# Power_Supply_And_Regulator.net
KiCad netlist of a schematic drawn in Altium Designer
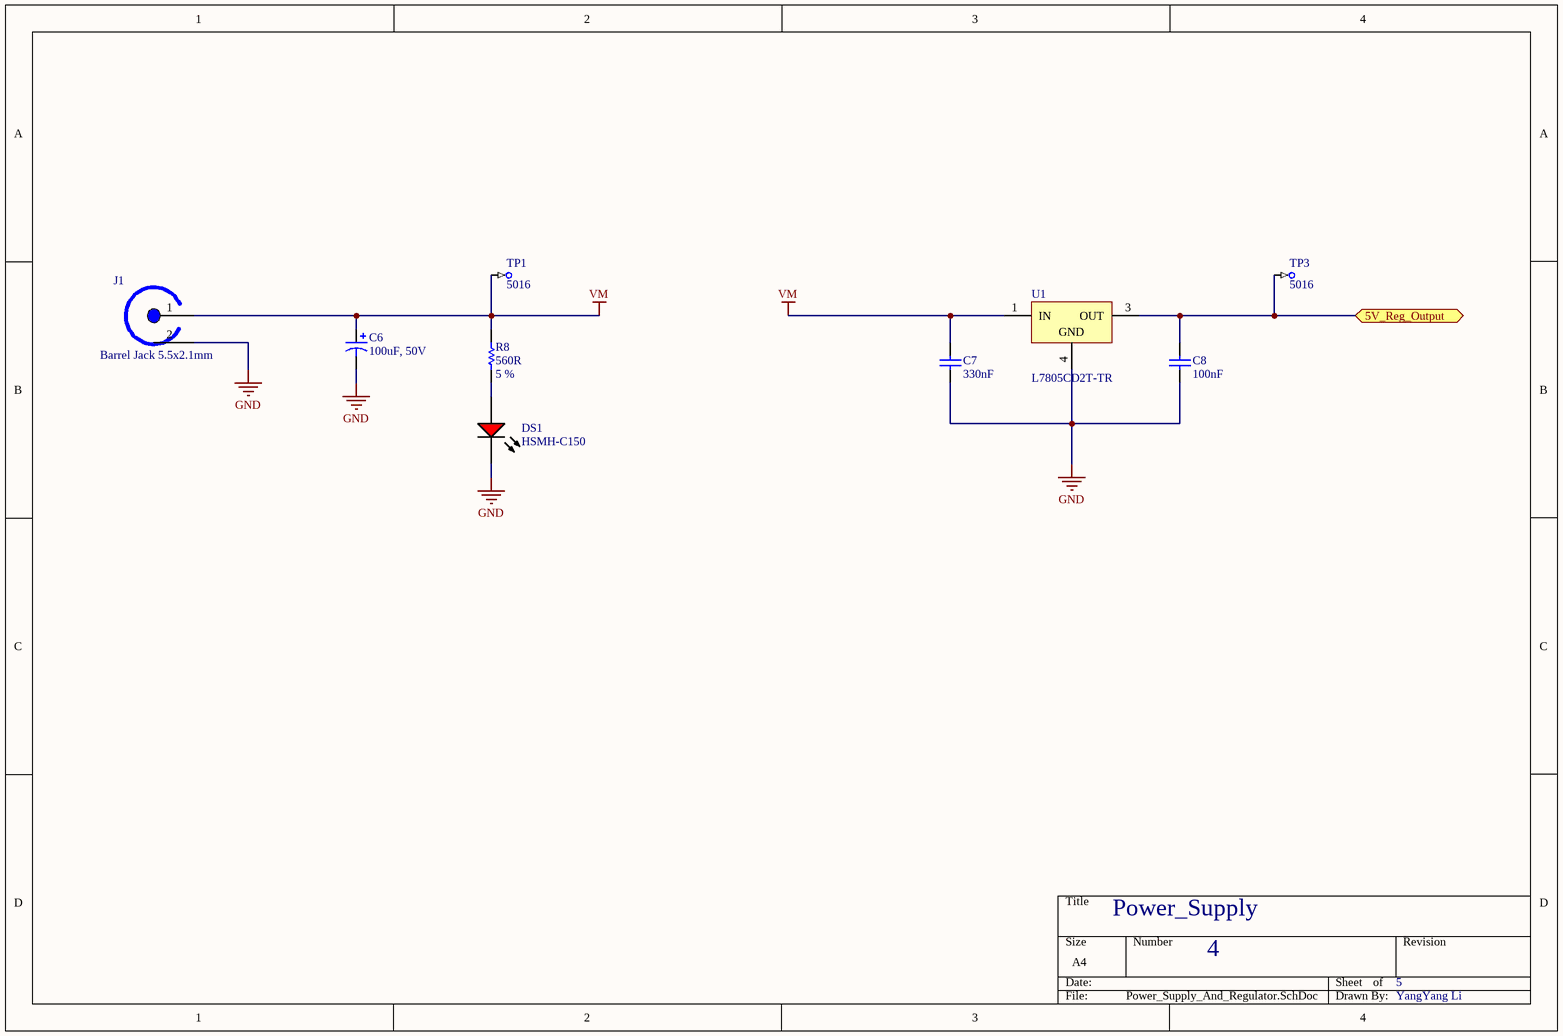
[diagram p0: Power_Supply_And_Regulator.SchDoc]

(export (version "E")
  (design (tool "Eeschema 10.0.6"))
  (components
    (comp (ref "C6")
      (value "100uF, 50V")
      (footprint "Capacitor radial 8mm")
      (description "Electrolytic Capacitor, 100 µF, 50 V, ± 20%, Radial Leaded, 8 mm")
      (libsource (lib "*") (part "Cap 100uF, 50V, THT radial"))
    )
    (comp (ref "C7")
      (value "330nF")
      (footprint "CAPC1608X87X35NL15T15")
      (description "C0603C334K4RACTU")
      (fields (field (name "MANUFACTURER") "Kemet"))
      (libsource (lib "Altium Content Vault") (part "CAP"))
    )
    (comp (ref "C8")
      (value "100nF")
      (footprint "CAPC2013X88X50NL20T25")
      (description "C0805C104K5RACTU")
      (fields (field (name "MANUFACTURER") "Kemet"))
      (libsource (lib "Altium Content Vault") (part "CAP"))
    )
    (comp (ref "DS1")
      (value "HSMH-C150")
      (footprint "AVAG-HSMX-C150_V")
      (description "LED Uni-Color Red, 65 mW, 25 mA, -40 to 85 degC, 2-Pin SMD, RoHS, Tape and Reel")
      (fields (field (name "MANUFACTURER") "Avago"))
      (libsource (lib "Altium Content Vault") (part "LED-RED-AK-2"))
    )
    (comp (ref "J1")
      (value "Barrel Jack 5.5x2.1mm")
      (footprint "Barrel Jack 2.1x5.5mm THT")
      (description "GCT DCJ200-10-A-K1-K")
      (libsource (lib "*") (part "Barrel Jack 5.5x2.1mm"))
    )
    (comp (ref "R8")
      (value "560R")
      (footprint "RESC1206(3216)_L")
      (description "560R 0.25W 5% 1206 (3216 Metric)  SMD")
      (fields
        (field (name "TOLERANCE") "5 %")
        (field (name "POWER") "0.25 W")
        (field (name "Comment") "560R 5% 1206(3216)")
      )
      (libsource (lib "Altium Content Vault") (part "RES"))
    )
    (comp (ref "TP1")
      (value "5016")
      (footprint "KEYSTONE-5016_V")
      (description "Test Point, 1-Pin SMT, RoHS, Tape and Reel")
      (fields (field (name "MANUFACTURER") "Keystone"))
      (libsource (lib "Altium Content Vault") (part "KEYSTONE-5016"))
    )
    (comp (ref "TP3")
      (value "5016")
      (footprint "KEYSTONE-5016_V")
      (description "Test Point, 1-Pin SMT, RoHS, Tape and Reel")
      (fields (field (name "MANUFACTURER") "Keystone"))
      (libsource (lib "Altium Content Vault") (part "KEYSTONE-5016"))
    )
    (comp (ref "U1")
      (value "L7805CD2T-TR")
      (footprint "TO-263_M")
      (description "Positive Voltage Regulator, 3-Pin D2PAK, Tape and Reel")
      (libsource (lib "Altium Content Vault") (part "PM-REG-L4940-SOT3"))
    )
  )
  (nets
    (net (code "1") (name "/5V_Reg_Output") (class "Default")
      (node (ref "C8") (pin "2") (pinfunction "2_2") (pintype "passive"))
      (node (ref "TP3") (pin "1") (pinfunction "1_1") (pintype "input"))
      (node (ref "U1") (pin "3") (pinfunction "OUT_3") (pintype "power_in"))
    )
    (net (code "2") (name "GND") (class "Default")
      (node (ref "C6") (pin "2") (pinfunction "2_2") (pintype "passive"))
      (node (ref "C7") (pin "1") (pinfunction "1_1") (pintype "passive"))
      (node (ref "C8") (pin "1") (pinfunction "1_1") (pintype "passive"))
      (node (ref "DS1") (pin "2") (pinfunction "K_2") (pintype "passive"))
      (node (ref "J1") (pin "2") (pinfunction "SLEEVE_2") (pintype "power_in"))
      (node (ref "U1") (pin "4") (pinfunction "GND_4") (pintype "power_in"))
    )
    (net (code "3") (name "Net-(DS1-A)") (class "Default")
      (node (ref "DS1") (pin "1") (pinfunction "A_1") (pintype "passive"))
      (node (ref "R8") (pin "1") (pinfunction "1_1") (pintype "passive"))
    )
    (net (code "4") (name "VM") (class "Default")
      (node (ref "C6") (pin "1") (pinfunction "1_1") (pintype "passive"))
      (node (ref "C7") (pin "2") (pinfunction "2_2") (pintype "passive"))
      (node (ref "J1") (pin "1") (pinfunction "TIP_1") (pintype "power_in"))
      (node (ref "R8") (pin "2") (pinfunction "2_2") (pintype "passive"))
      (node (ref "TP1") (pin "1") (pinfunction "1_1") (pintype "input"))
      (node (ref "U1") (pin "1") (pinfunction "IN_1") (pintype "power_in"))
    )
  )
)
